# 5-Band_50W_PA_LC_Lowpass_Filters.net
KiCad netlist of a schematic drawn in EAGLE
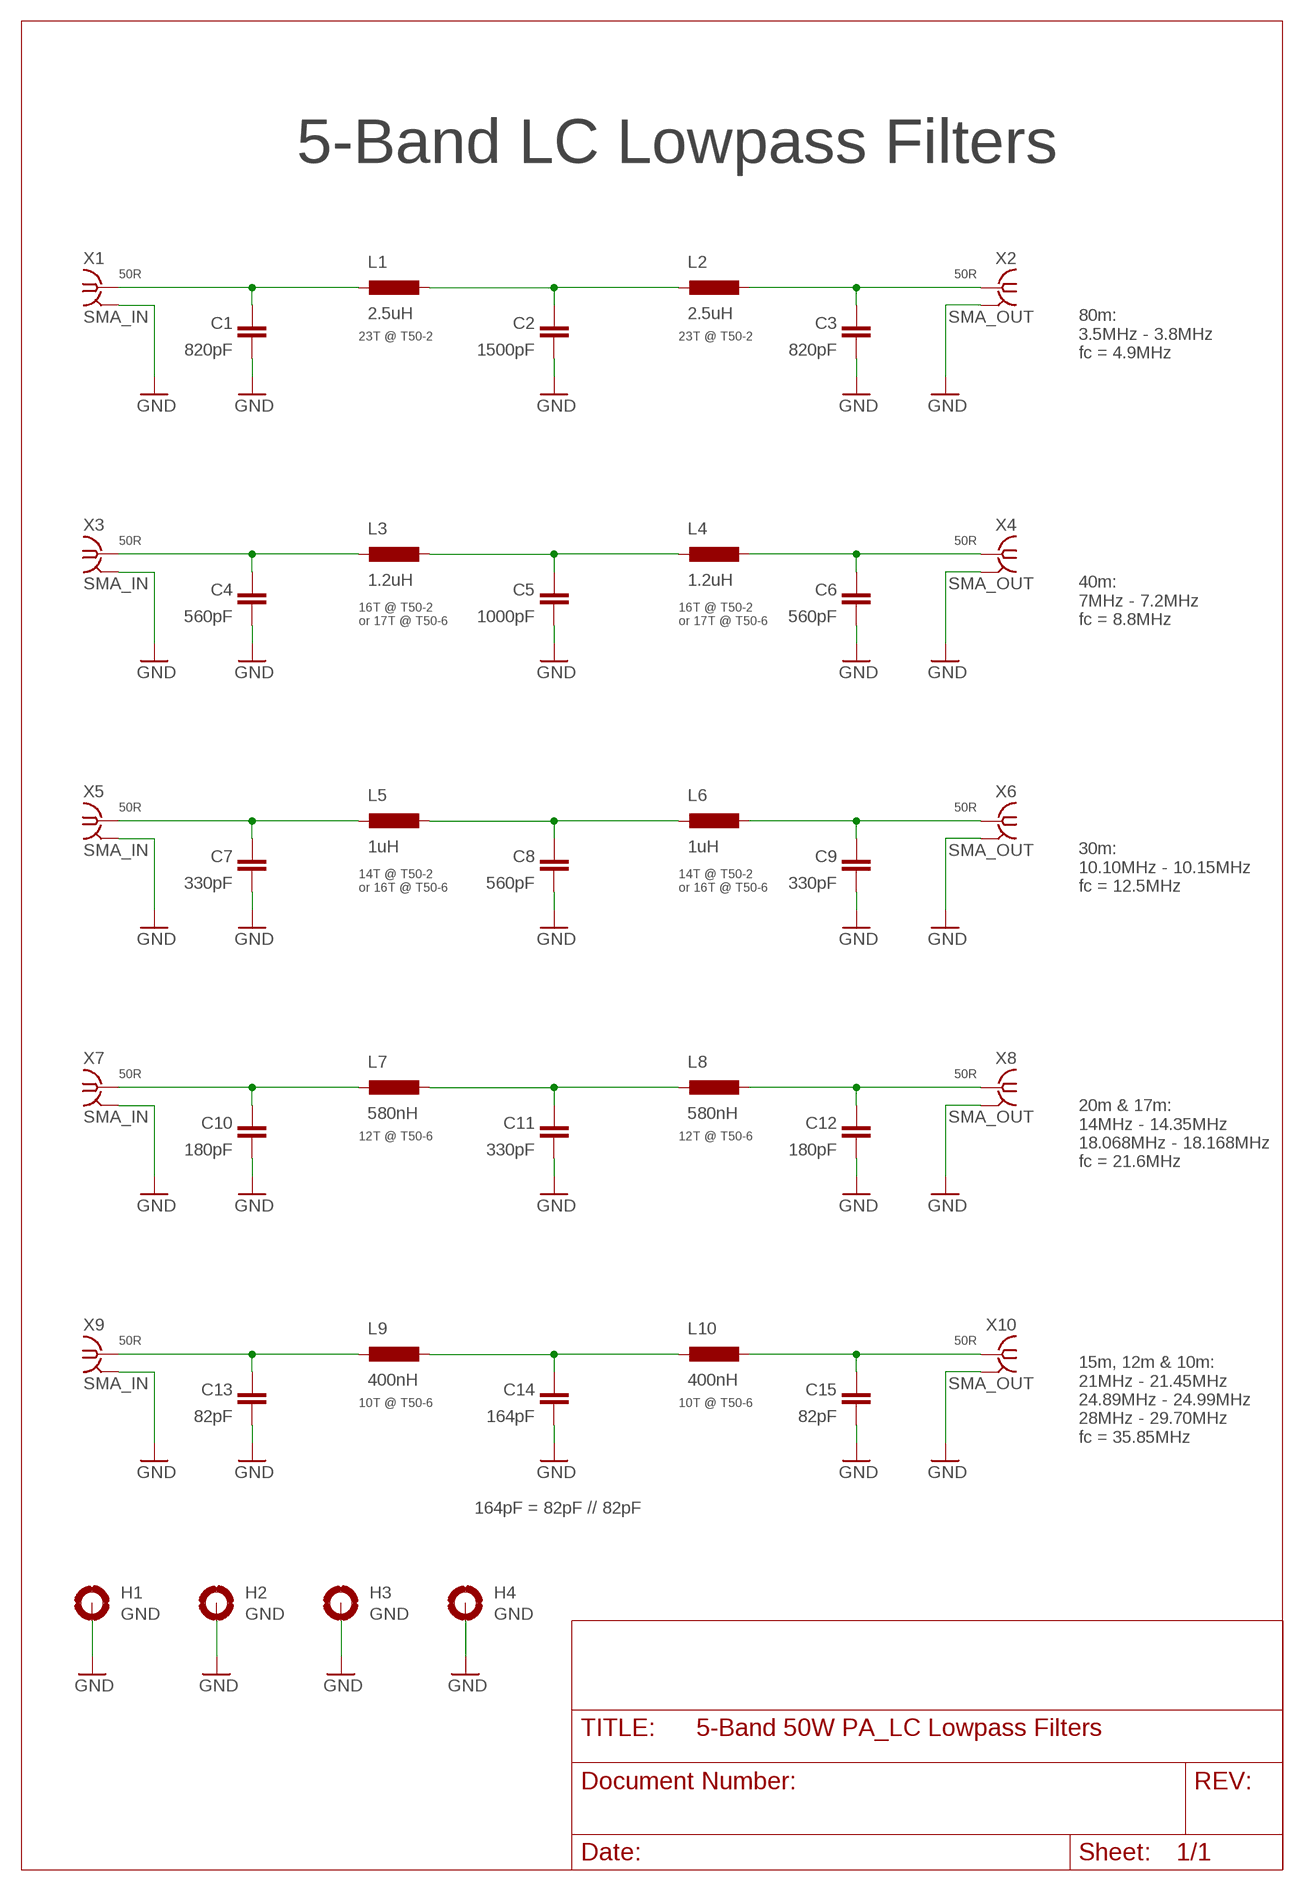
[diagram p0: schematic, sheet 1]

(export (version "E")
  (design (tool "Eeschema 10.0.6"))
  (components
    (comp (ref "C1")
      (value "820pF")
      (footprint "eagle-import:C1206K")
      (libsource (lib "eagle-import") (part "C-EUC1206K"))
    )
    (comp (ref "C2")
      (value "1500pF")
      (footprint "eagle-import:C1206K")
      (libsource (lib "eagle-import") (part "C-EUC1206K"))
    )
    (comp (ref "C3")
      (value "820pF")
      (footprint "eagle-import:C1206K")
      (libsource (lib "eagle-import") (part "C-EUC1206K"))
    )
    (comp (ref "C4")
      (value "560pF")
      (footprint "eagle-import:C1206K")
      (libsource (lib "eagle-import") (part "C-EUC1206K"))
    )
    (comp (ref "C5")
      (value "1000pF")
      (footprint "eagle-import:C1206K")
      (libsource (lib "eagle-import") (part "C-EUC1206K"))
    )
    (comp (ref "C6")
      (value "560pF")
      (footprint "eagle-import:C1206K")
      (libsource (lib "eagle-import") (part "C-EUC1206K"))
    )
    (comp (ref "C7")
      (value "330pF")
      (footprint "eagle-import:C1206K")
      (libsource (lib "eagle-import") (part "C-EUC1206K"))
    )
    (comp (ref "C8")
      (value "560pF")
      (footprint "eagle-import:C1206K")
      (libsource (lib "eagle-import") (part "C-EUC1206K"))
    )
    (comp (ref "C9")
      (value "330pF")
      (footprint "eagle-import:C1206K")
      (libsource (lib "eagle-import") (part "C-EUC1206K"))
    )
    (comp (ref "C10")
      (value "180pF")
      (footprint "eagle-import:C1206K")
      (libsource (lib "eagle-import") (part "C-EUC1206K"))
    )
    (comp (ref "C11")
      (value "330pF")
      (footprint "eagle-import:C1206K")
      (libsource (lib "eagle-import") (part "C-EUC1206K"))
    )
    (comp (ref "C12")
      (value "180pF")
      (footprint "eagle-import:C1206K")
      (libsource (lib "eagle-import") (part "C-EUC1206K"))
    )
    (comp (ref "C13")
      (value "82pF")
      (footprint "eagle-import:C1206K")
      (libsource (lib "eagle-import") (part "C-EUC1206K"))
    )
    (comp (ref "C14")
      (value "164pF")
      (footprint "eagle-import:C1206K")
      (libsource (lib "eagle-import") (part "C-EUC1206K"))
    )
    (comp (ref "C15")
      (value "82pF")
      (footprint "eagle-import:C1206K")
      (libsource (lib "eagle-import") (part "C-EUC1206K"))
    )
    (comp (ref "H1")
      (value "GND")
      (footprint "eagle-import:3,0-PAD")
      (libsource (lib "eagle-import") (part "MOUNT-PAD-ROUND3.0"))
    )
    (comp (ref "H2")
      (value "GND")
      (footprint "eagle-import:3,0-PAD")
      (libsource (lib "eagle-import") (part "MOUNT-PAD-ROUND3.0"))
    )
    (comp (ref "H3")
      (value "GND")
      (footprint "eagle-import:3,0-PAD")
      (libsource (lib "eagle-import") (part "MOUNT-PAD-ROUND3.0"))
    )
    (comp (ref "H4")
      (value "GND")
      (footprint "eagle-import:3,0-PAD")
      (libsource (lib "eagle-import") (part "MOUNT-PAD-ROUND3.0"))
    )
    (comp (ref "L1")
      (value "2.5uH")
      (footprint "eagle-import:T50-6SMD")
      (libsource (lib "eagle-import") (part "T50-6"))
    )
    (comp (ref "L2")
      (value "2.5uH")
      (footprint "eagle-import:T50-6SMD")
      (libsource (lib "eagle-import") (part "T50-6"))
    )
    (comp (ref "L3")
      (value "1.2uH")
      (footprint "eagle-import:T50-6SMD")
      (libsource (lib "eagle-import") (part "T50-6"))
    )
    (comp (ref "L4")
      (value "1.2uH")
      (footprint "eagle-import:T50-6SMD")
      (libsource (lib "eagle-import") (part "T50-6"))
    )
    (comp (ref "L5")
      (value "1uH")
      (footprint "eagle-import:T50-6SMD")
      (libsource (lib "eagle-import") (part "T50-6"))
    )
    (comp (ref "L6")
      (value "1uH")
      (footprint "eagle-import:T50-6SMD")
      (libsource (lib "eagle-import") (part "T50-6"))
    )
    (comp (ref "L7")
      (value "580nH")
      (footprint "eagle-import:T50-6SMD")
      (libsource (lib "eagle-import") (part "T50-6"))
    )
    (comp (ref "L8")
      (value "580nH")
      (footprint "eagle-import:T50-6SMD")
      (libsource (lib "eagle-import") (part "T50-6"))
    )
    (comp (ref "L9")
      (value "400nH")
      (footprint "eagle-import:T50-6SMD")
      (libsource (lib "eagle-import") (part "T50-6"))
    )
    (comp (ref "L10")
      (value "400nH")
      (footprint "eagle-import:T50-6SMD")
      (libsource (lib "eagle-import") (part "T50-6"))
    )
    (comp (ref "X1")
      (value "SMA_IN")
      (footprint "eagle-import:J502-ND-142-0711-821_826")
      (fields (field (name "MF") "JOHNSON COMPONENTS") (field (name "MPN") "142-0711-821"))
      (libsource (lib "eagle-import") (part "SMA-142-0711-821/826"))
    )
    (comp (ref "X2")
      (value "SMA_OUT")
      (footprint "eagle-import:J502-ND-142-0711-821_826")
      (fields (field (name "MF") "JOHNSON COMPONENTS") (field (name "MPN") "142-0711-821"))
      (libsource (lib "eagle-import") (part "SMA-142-0711-821/826"))
    )
    (comp (ref "X3")
      (value "SMA_IN")
      (footprint "eagle-import:J502-ND-142-0711-821_826")
      (fields (field (name "MF") "JOHNSON COMPONENTS") (field (name "MPN") "142-0711-821"))
      (libsource (lib "eagle-import") (part "SMA-142-0711-821/826"))
    )
    (comp (ref "X4")
      (value "SMA_OUT")
      (footprint "eagle-import:J502-ND-142-0711-821_826")
      (fields (field (name "MF") "JOHNSON COMPONENTS") (field (name "MPN") "142-0711-821"))
      (libsource (lib "eagle-import") (part "SMA-142-0711-821/826"))
    )
    (comp (ref "X5")
      (value "SMA_IN")
      (footprint "eagle-import:J502-ND-142-0711-821_826")
      (fields (field (name "MF") "JOHNSON COMPONENTS") (field (name "MPN") "142-0711-821"))
      (libsource (lib "eagle-import") (part "SMA-142-0711-821/826"))
    )
    (comp (ref "X6")
      (value "SMA_OUT")
      (footprint "eagle-import:J502-ND-142-0711-821_826")
      (fields (field (name "MF") "JOHNSON COMPONENTS") (field (name "MPN") "142-0711-821"))
      (libsource (lib "eagle-import") (part "SMA-142-0711-821/826"))
    )
    (comp (ref "X7")
      (value "SMA_IN")
      (footprint "eagle-import:J502-ND-142-0711-821_826")
      (fields (field (name "MF") "JOHNSON COMPONENTS") (field (name "MPN") "142-0711-821"))
      (libsource (lib "eagle-import") (part "SMA-142-0711-821/826"))
    )
    (comp (ref "X8")
      (value "SMA_OUT")
      (footprint "eagle-import:J502-ND-142-0711-821_826")
      (fields (field (name "MF") "JOHNSON COMPONENTS") (field (name "MPN") "142-0711-821"))
      (libsource (lib "eagle-import") (part "SMA-142-0711-821/826"))
    )
    (comp (ref "X9")
      (value "SMA_IN")
      (footprint "eagle-import:J502-ND-142-0711-821_826")
      (fields (field (name "MF") "JOHNSON COMPONENTS") (field (name "MPN") "142-0711-821"))
      (libsource (lib "eagle-import") (part "SMA-142-0711-821/826"))
    )
    (comp (ref "X10")
      (value "SMA_OUT")
      (footprint "eagle-import:J502-ND-142-0711-821_826")
      (fields (field (name "MF") "JOHNSON COMPONENTS") (field (name "MPN") "142-0711-821"))
      (libsource (lib "eagle-import") (part "SMA-142-0711-821/826"))
    )
  )
  (nets
    (net (code "1") (name "GND") (class "Default")
      (node (ref "C1") (pin "1") (pinfunction "1_1") (pintype "passive"))
      (node (ref "C10") (pin "1") (pinfunction "1_1") (pintype "passive"))
      (node (ref "C11") (pin "1") (pinfunction "1_1") (pintype "passive"))
      (node (ref "C12") (pin "1") (pinfunction "1_1") (pintype "passive"))
      (node (ref "C13") (pin "1") (pinfunction "1_1") (pintype "passive"))
      (node (ref "C14") (pin "1") (pinfunction "1_1") (pintype "passive"))
      (node (ref "C15") (pin "1") (pinfunction "1_1") (pintype "passive"))
      (node (ref "C2") (pin "1") (pinfunction "1_1") (pintype "passive"))
      (node (ref "C3") (pin "1") (pinfunction "1_1") (pintype "passive"))
      (node (ref "C4") (pin "1") (pinfunction "1_1") (pintype "passive"))
      (node (ref "C5") (pin "1") (pinfunction "1_1") (pintype "passive"))
      (node (ref "C6") (pin "1") (pinfunction "1_1") (pintype "passive"))
      (node (ref "C7") (pin "1") (pinfunction "1_1") (pintype "passive"))
      (node (ref "C8") (pin "1") (pinfunction "1_1") (pintype "passive"))
      (node (ref "C9") (pin "1") (pinfunction "1_1") (pintype "passive"))
      (node (ref "H1") (pin "B3,0") (pinfunction "MOUNT_B3,0") (pintype "passive"))
      (node (ref "H2") (pin "B3,0") (pinfunction "MOUNT_B3,0") (pintype "passive"))
      (node (ref "H3") (pin "B3,0") (pinfunction "MOUNT_B3,0") (pintype "passive"))
      (node (ref "H4") (pin "B3,0") (pinfunction "MOUNT_B3,0") (pintype "passive"))
      (node (ref "X1") (pin "G@1") (pinfunction "2_G@1") (pintype "passive"))
      (node (ref "X1") (pin "G@2") (pinfunction "2_G@2") (pintype "passive"))
      (node (ref "X1") (pin "G@3") (pinfunction "2_G@3") (pintype "passive"))
      (node (ref "X1") (pin "G@4") (pinfunction "2_G@4") (pintype "passive"))
      (node (ref "X10") (pin "G@1") (pinfunction "2_G@1") (pintype "passive"))
      (node (ref "X10") (pin "G@2") (pinfunction "2_G@2") (pintype "passive"))
      (node (ref "X10") (pin "G@3") (pinfunction "2_G@3") (pintype "passive"))
      (node (ref "X10") (pin "G@4") (pinfunction "2_G@4") (pintype "passive"))
      (node (ref "X2") (pin "G@1") (pinfunction "2_G@1") (pintype "passive"))
      (node (ref "X2") (pin "G@2") (pinfunction "2_G@2") (pintype "passive"))
      (node (ref "X2") (pin "G@3") (pinfunction "2_G@3") (pintype "passive"))
      (node (ref "X2") (pin "G@4") (pinfunction "2_G@4") (pintype "passive"))
      (node (ref "X3") (pin "G@1") (pinfunction "2_G@1") (pintype "passive"))
      (node (ref "X3") (pin "G@2") (pinfunction "2_G@2") (pintype "passive"))
      (node (ref "X3") (pin "G@3") (pinfunction "2_G@3") (pintype "passive"))
      (node (ref "X3") (pin "G@4") (pinfunction "2_G@4") (pintype "passive"))
      (node (ref "X4") (pin "G@1") (pinfunction "2_G@1") (pintype "passive"))
      (node (ref "X4") (pin "G@2") (pinfunction "2_G@2") (pintype "passive"))
      (node (ref "X4") (pin "G@3") (pinfunction "2_G@3") (pintype "passive"))
      (node (ref "X4") (pin "G@4") (pinfunction "2_G@4") (pintype "passive"))
      (node (ref "X5") (pin "G@1") (pinfunction "2_G@1") (pintype "passive"))
      (node (ref "X5") (pin "G@2") (pinfunction "2_G@2") (pintype "passive"))
      (node (ref "X5") (pin "G@3") (pinfunction "2_G@3") (pintype "passive"))
      (node (ref "X5") (pin "G@4") (pinfunction "2_G@4") (pintype "passive"))
      (node (ref "X6") (pin "G@1") (pinfunction "2_G@1") (pintype "passive"))
      (node (ref "X6") (pin "G@2") (pinfunction "2_G@2") (pintype "passive"))
      (node (ref "X6") (pin "G@3") (pinfunction "2_G@3") (pintype "passive"))
      (node (ref "X6") (pin "G@4") (pinfunction "2_G@4") (pintype "passive"))
      (node (ref "X7") (pin "G@1") (pinfunction "2_G@1") (pintype "passive"))
      (node (ref "X7") (pin "G@2") (pinfunction "2_G@2") (pintype "passive"))
      (node (ref "X7") (pin "G@3") (pinfunction "2_G@3") (pintype "passive"))
      (node (ref "X7") (pin "G@4") (pinfunction "2_G@4") (pintype "passive"))
      (node (ref "X8") (pin "G@1") (pinfunction "2_G@1") (pintype "passive"))
      (node (ref "X8") (pin "G@2") (pinfunction "2_G@2") (pintype "passive"))
      (node (ref "X8") (pin "G@3") (pinfunction "2_G@3") (pintype "passive"))
      (node (ref "X8") (pin "G@4") (pinfunction "2_G@4") (pintype "passive"))
      (node (ref "X9") (pin "G@1") (pinfunction "2_G@1") (pintype "passive"))
      (node (ref "X9") (pin "G@2") (pinfunction "2_G@2") (pintype "passive"))
      (node (ref "X9") (pin "G@3") (pinfunction "2_G@3") (pintype "passive"))
      (node (ref "X9") (pin "G@4") (pinfunction "2_G@4") (pintype "passive"))
    )
    (net (code "2") (name "Net-(L1-1)") (class "Default")
      (node (ref "C1") (pin "2") (pinfunction "2_2") (pintype "passive"))
      (node (ref "L1") (pin "P$1") (pinfunction "1_P$1") (pintype "passive"))
      (node (ref "X1") (pin "1") (pinfunction "1_1") (pintype "passive"))
    )
    (net (code "3") (name "Net-(L1-2)") (class "Default")
      (node (ref "C2") (pin "2") (pinfunction "2_2") (pintype "passive"))
      (node (ref "L1") (pin "P$2") (pinfunction "2_P$2") (pintype "passive"))
      (node (ref "L2") (pin "P$1") (pinfunction "1_P$1") (pintype "passive"))
    )
    (net (code "4") (name "Net-(L2-2)") (class "Default")
      (node (ref "C3") (pin "2") (pinfunction "2_2") (pintype "passive"))
      (node (ref "L2") (pin "P$2") (pinfunction "2_P$2") (pintype "passive"))
      (node (ref "X2") (pin "1") (pinfunction "1_1") (pintype "passive"))
    )
    (net (code "5") (name "Net-(L3-1)") (class "Default")
      (node (ref "C4") (pin "2") (pinfunction "2_2") (pintype "passive"))
      (node (ref "L3") (pin "P$1") (pinfunction "1_P$1") (pintype "passive"))
      (node (ref "X3") (pin "1") (pinfunction "1_1") (pintype "passive"))
    )
    (net (code "6") (name "Net-(L3-2)") (class "Default")
      (node (ref "C5") (pin "2") (pinfunction "2_2") (pintype "passive"))
      (node (ref "L3") (pin "P$2") (pinfunction "2_P$2") (pintype "passive"))
      (node (ref "L4") (pin "P$1") (pinfunction "1_P$1") (pintype "passive"))
    )
    (net (code "7") (name "Net-(L4-2)") (class "Default")
      (node (ref "C6") (pin "2") (pinfunction "2_2") (pintype "passive"))
      (node (ref "L4") (pin "P$2") (pinfunction "2_P$2") (pintype "passive"))
      (node (ref "X4") (pin "1") (pinfunction "1_1") (pintype "passive"))
    )
    (net (code "8") (name "Net-(L5-1)") (class "Default")
      (node (ref "C7") (pin "2") (pinfunction "2_2") (pintype "passive"))
      (node (ref "L5") (pin "P$1") (pinfunction "1_P$1") (pintype "passive"))
      (node (ref "X5") (pin "1") (pinfunction "1_1") (pintype "passive"))
    )
    (net (code "9") (name "Net-(L5-2)") (class "Default")
      (node (ref "C8") (pin "2") (pinfunction "2_2") (pintype "passive"))
      (node (ref "L5") (pin "P$2") (pinfunction "2_P$2") (pintype "passive"))
      (node (ref "L6") (pin "P$1") (pinfunction "1_P$1") (pintype "passive"))
    )
    (net (code "10") (name "Net-(L6-2)") (class "Default")
      (node (ref "C9") (pin "2") (pinfunction "2_2") (pintype "passive"))
      (node (ref "L6") (pin "P$2") (pinfunction "2_P$2") (pintype "passive"))
      (node (ref "X6") (pin "1") (pinfunction "1_1") (pintype "passive"))
    )
    (net (code "11") (name "Net-(L7-1)") (class "Default")
      (node (ref "C10") (pin "2") (pinfunction "2_2") (pintype "passive"))
      (node (ref "L7") (pin "P$1") (pinfunction "1_P$1") (pintype "passive"))
      (node (ref "X7") (pin "1") (pinfunction "1_1") (pintype "passive"))
    )
    (net (code "12") (name "Net-(L7-2)") (class "Default")
      (node (ref "C11") (pin "2") (pinfunction "2_2") (pintype "passive"))
      (node (ref "L7") (pin "P$2") (pinfunction "2_P$2") (pintype "passive"))
      (node (ref "L8") (pin "P$1") (pinfunction "1_P$1") (pintype "passive"))
    )
    (net (code "13") (name "Net-(L8-2)") (class "Default")
      (node (ref "C12") (pin "2") (pinfunction "2_2") (pintype "passive"))
      (node (ref "L8") (pin "P$2") (pinfunction "2_P$2") (pintype "passive"))
      (node (ref "X8") (pin "1") (pinfunction "1_1") (pintype "passive"))
    )
    (net (code "14") (name "Net-(L9-1)") (class "Default")
      (node (ref "C13") (pin "2") (pinfunction "2_2") (pintype "passive"))
      (node (ref "L9") (pin "P$1") (pinfunction "1_P$1") (pintype "passive"))
      (node (ref "X9") (pin "1") (pinfunction "1_1") (pintype "passive"))
    )
    (net (code "15") (name "Net-(L10-1)") (class "Default")
      (node (ref "C14") (pin "2") (pinfunction "2_2") (pintype "passive"))
      (node (ref "L10") (pin "P$1") (pinfunction "1_P$1") (pintype "passive"))
      (node (ref "L9") (pin "P$2") (pinfunction "2_P$2") (pintype "passive"))
    )
    (net (code "16") (name "Net-(L10-2)") (class "Default")
      (node (ref "C15") (pin "2") (pinfunction "2_2") (pintype "passive"))
      (node (ref "L10") (pin "P$2") (pinfunction "2_P$2") (pintype "passive"))
      (node (ref "X10") (pin "1") (pinfunction "1_1") (pintype "passive"))
    )
  )
)
